# Communications.net
KiCad netlist of a schematic drawn in Altium Designer
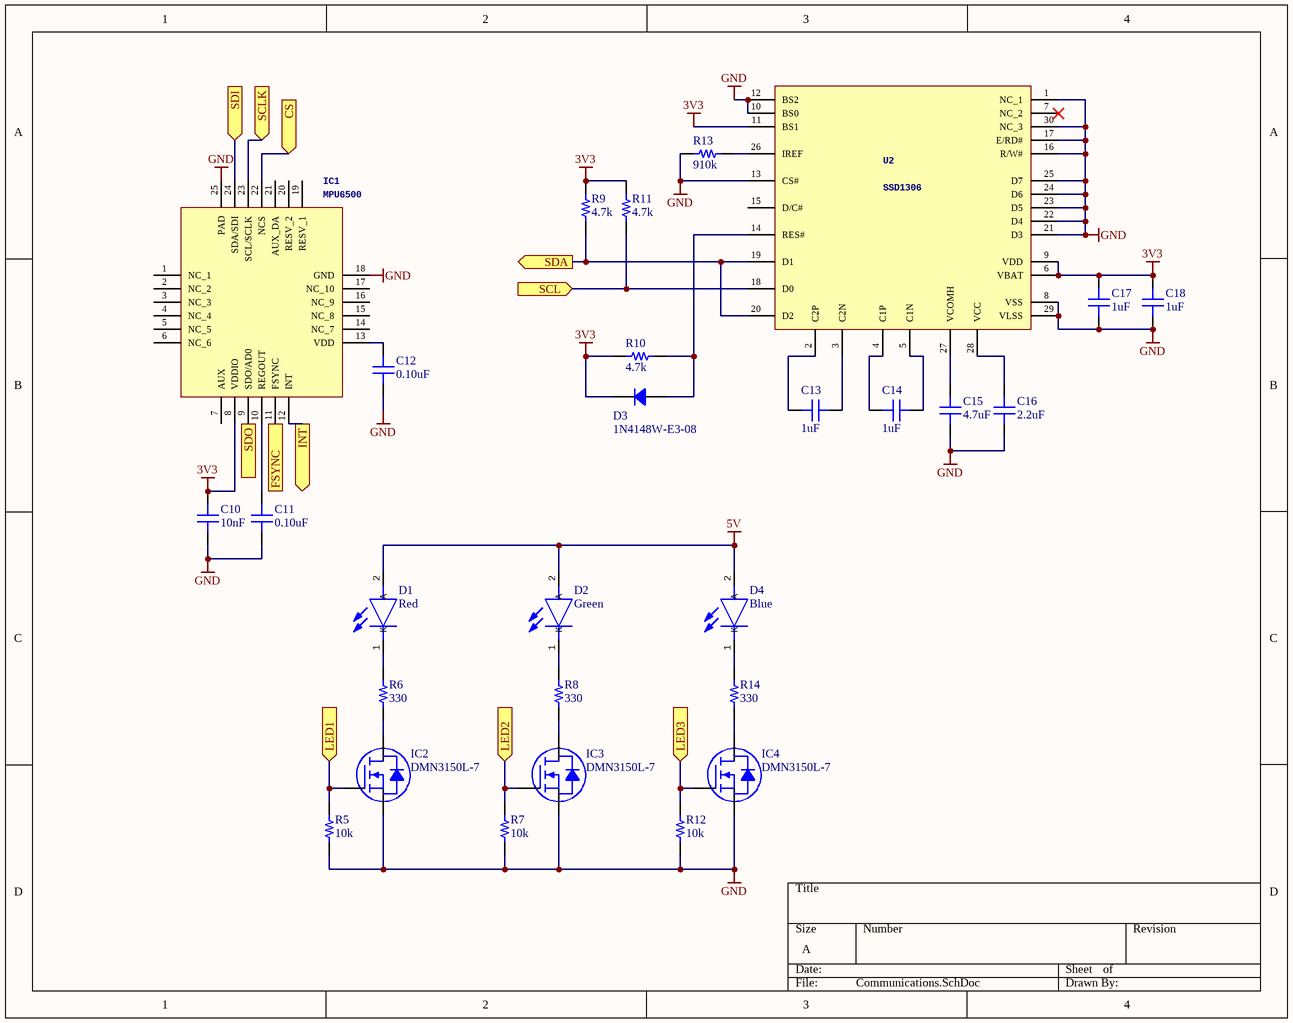
[diagram p0: Communications.SchDoc]

(export (version "E")
  (design (tool "Eeschema 10.0.6"))
  (components
    (comp (ref "C10")
      (value "10nF")
      (footprint "CAP 0402/1005")
      (description "CAP CER 10000PF 16V X7R 0402")
      (fields
        (field (name "PART NUMBER") "CL05B103KO5NNNC")
        (field (name "MANUFACTURER") "Samsung Electro-Mechanics America, Inc.")
      )
      (libsource (lib "Celestial Library Database") (part "Capacitor"))
    )
    (comp (ref "C11")
      (value "0.10uF")
      (footprint "CAP 0402/1005")
      (description "CAP CER 0.1UF 16V X7R 0402")
      (fields
        (field (name "PART NUMBER") "GCM155R71C104KA55D")
        (field (name "MANUFACTURER") "Murata Electronics North America")
      )
      (libsource (lib "Celestial Library Database") (part "Capacitor"))
    )
    (comp (ref "C12")
      (value "0.10uF")
      (footprint "CAP 0402/1005")
      (description "CAP CER 0.1UF 16V X7R 0402")
      (fields
        (field (name "PART NUMBER") "GCM155R71C104KA55D")
        (field (name "MANUFACTURER") "Murata Electronics North America")
      )
      (libsource (lib "Celestial Library Database") (part "Capacitor"))
    )
    (comp (ref "C13")
      (value "1uF")
      (footprint "CAP 0603/1608")
      (description "CAP CER 1UF 10V Y5V 0603")
      (fields
        (field (name "PART NUMBER") "CL10F105ZP8NNNC")
        (field (name "MANUFACTURER") "Samsung Electro-Mechanics America, Inc.")
      )
      (libsource (lib "Celestial Library Database") (part "Capacitor"))
    )
    (comp (ref "C14")
      (value "1uF")
      (footprint "CAP 0603/1608")
      (description "CAP CER 1UF 10V Y5V 0603")
      (fields
        (field (name "PART NUMBER") "CL10F105ZP8NNNC")
        (field (name "MANUFACTURER") "Samsung Electro-Mechanics America, Inc.")
      )
      (libsource (lib "Celestial Library Database") (part "Capacitor"))
    )
    (comp (ref "C15")
      (value "4.7uF")
      (footprint "CAP 0805/2012")
      (description "CAP CER 4.7UF 10V Y5V 0805")
      (fields (field (name "PART NUMBER") "CC0805ZRY5V6BB475") (field (name "MANUFACTURER") "Yageo"))
      (libsource (lib "Celestial Library Database") (part "Capacitor"))
    )
    (comp (ref "C16")
      (value "2.2uF")
      (footprint "CAP 0402/1005")
      (description "CAP CER 2.2UF 10V X5R 0402")
      (fields
        (field (name "PART NUMBER") "CL05A225KP5NSNC")
        (field (name "MANUFACTURER") "Samsung Electro-Mechanics America, Inc.")
      )
      (libsource (lib "Celestial Library Database") (part "Capacitor"))
    )
    (comp (ref "C17")
      (value "1uF")
      (footprint "CAP 0603/1608")
      (description "CAP CER 1UF 10V Y5V 0603")
      (fields
        (field (name "PART NUMBER") "CL10F105ZP8NNNC")
        (field (name "MANUFACTURER") "Samsung Electro-Mechanics America, Inc.")
      )
      (libsource (lib "Celestial Library Database") (part "Capacitor"))
    )
    (comp (ref "C18")
      (value "1uF")
      (footprint "CAP 0603/1608")
      (description "CAP CER 1UF 10V Y5V 0603")
      (fields
        (field (name "PART NUMBER") "CL10F105ZP8NNNC")
        (field (name "MANUFACTURER") "Samsung Electro-Mechanics America, Inc.")
      )
      (libsource (lib "Celestial Library Database") (part "Capacitor"))
    )
    (comp (ref "D1")
      (value "Red")
      (footprint "LTST")
      (libsource (lib "micromousev2Parts") (part "GENERIC_LED"))
    )
    (comp (ref "D2")
      (value "Green")
      (footprint "LTST")
      (libsource (lib "micromousev2Parts") (part "GENERIC_LED"))
    )
    (comp (ref "D3")
      (value "1N4148W-E3-08")
      (footprint "SOD-123")
      (description "DIODE GEN PURP 75V 150MA SOD123")
      (fields (field (name "MANUFACTURER") "Vishay Semiconductor Diodes Division"))
      (libsource (lib "Celestial Library Database") (part "Diode"))
    )
    (comp (ref "D4")
      (value "Blue")
      (footprint "LTST")
      (libsource (lib "micromousev2Parts") (part "GENERIC_LED"))
    )
    (comp (ref "IC1")
      (value "MPU6500")
      (footprint "QFN40P300X300X95-25N")
      (fields (field (name "ARROW_PART_NUMBER") "MPU-6500") (field (name "LIBRARYNAME") "micromousev2Parts"))
      (libsource (lib "micromousev2Parts") (part "MPU-6500"))
    )
    (comp (ref "IC2")
      (value "DMN3150L-7")
      (footprint "DIODES SOT-23-3")
      (description "MOSFET N-CH 28V 3.2A SOT23-3")
      (fields (field (name "MANUFACTURER") "Diodes Incorporated"))
      (libsource (lib "Celestial Library Database") (part "DIODES INC MOSFET N-CH SOT-23-3"))
    )
    (comp (ref "IC3")
      (value "DMN3150L-7")
      (footprint "DIODES SOT-23-3")
      (description "MOSFET N-CH 28V 3.2A SOT23-3")
      (fields (field (name "MANUFACTURER") "Diodes Incorporated"))
      (libsource (lib "Celestial Library Database") (part "DIODES INC MOSFET N-CH SOT-23-3"))
    )
    (comp (ref "IC4")
      (value "DMN3150L-7")
      (footprint "DIODES SOT-23-3")
      (description "MOSFET N-CH 28V 3.2A SOT23-3")
      (fields (field (name "MANUFACTURER") "Diodes Incorporated"))
      (libsource (lib "Celestial Library Database") (part "DIODES INC MOSFET N-CH SOT-23-3"))
    )
    (comp (ref "R5")
      (value "10k")
      (footprint "RES 0402/1005")
      (description "RES SMD 10K OHM 5% 1/16W 0402")
      (fields (field (name "PART NUMBER") "RC0402JR-0710KL") (field (name "MANUFACTURER") "Yageo"))
      (libsource (lib "Celestial Library Database") (part "Resistor"))
    )
    (comp (ref "R6")
      (value "330")
      (footprint "RES 0402/1005")
      (fields
        (field (name "PART NUMBER") "RMCF0402JT330R")
        (field (name "MANUFACTURER") "Stackpole Electronics Inc.")
      )
      (libsource (lib "Celestial Library Database") (part "Resistor"))
    )
    (comp (ref "R7")
      (value "10k")
      (footprint "RES 0402/1005")
      (description "RES SMD 10K OHM 5% 1/16W 0402")
      (fields (field (name "PART NUMBER") "RC0402JR-0710KL") (field (name "MANUFACTURER") "Yageo"))
      (libsource (lib "Celestial Library Database") (part "Resistor"))
    )
    (comp (ref "R8")
      (value "330")
      (footprint "RES 0402/1005")
      (fields
        (field (name "PART NUMBER") "RMCF0402JT330R")
        (field (name "MANUFACTURER") "Stackpole Electronics Inc.")
      )
      (libsource (lib "Celestial Library Database") (part "Resistor"))
    )
    (comp (ref "R9")
      (value "4.7k")
      (footprint "RES 0603/1608")
      (description "RES SMD 4.7K OHM 1% 1/10W 0603")
      (fields
        (field (name "PART NUMBER") "ERJ-3EKF4701V")
        (field (name "MANUFACTURER") "Panasonic Electronic Components")
      )
      (libsource (lib "Celestial Library Database") (part "Resistor"))
    )
    (comp (ref "R10")
      (value "4.7k")
      (footprint "RES 0603/1608")
      (description "RES SMD 4.7K OHM 1% 1/10W 0603")
      (fields
        (field (name "PART NUMBER") "ERJ-3EKF4701V")
        (field (name "MANUFACTURER") "Panasonic Electronic Components")
      )
      (libsource (lib "Celestial Library Database") (part "Resistor"))
    )
    (comp (ref "R11")
      (value "4.7k")
      (footprint "RES 0603/1608")
      (description "RES SMD 4.7K OHM 1% 1/10W 0603")
      (fields
        (field (name "PART NUMBER") "ERJ-3EKF4701V")
        (field (name "MANUFACTURER") "Panasonic Electronic Components")
      )
      (libsource (lib "Celestial Library Database") (part "Resistor"))
    )
    (comp (ref "R12")
      (value "10k")
      (footprint "RES 0402/1005")
      (description "RES SMD 10K OHM 5% 1/16W 0402")
      (fields (field (name "PART NUMBER") "RC0402JR-0710KL") (field (name "MANUFACTURER") "Yageo"))
      (libsource (lib "Celestial Library Database") (part "Resistor"))
    )
    (comp (ref "R13")
      (value "910k")
      (footprint "RES 0402/1005")
      (description "RES SMD 910K OHM 5% 1/10W 0402")
      (fields
        (field (name "PART NUMBER") "ERJ-2GEJ914X")
        (field (name "MANUFACTURER") "Panasonic Electronic Components")
      )
      (libsource (lib "Celestial Library Database") (part "Resistor"))
    )
    (comp (ref "R14")
      (value "330")
      (footprint "RES 0402/1005")
      (fields
        (field (name "PART NUMBER") "RMCF0402JT330R")
        (field (name "MANUFACTURER") "Stackpole Electronics Inc.")
      )
      (libsource (lib "Celestial Library Database") (part "Resistor"))
    )
    (comp (ref "U2")
      (value "SSD1306")
      (footprint "30PINFPC_P0.7MM")
      (fields (field (name "LIBRARYNAME") "micromousev2Parts"))
      (libsource (lib "micromousev2Parts") (part "SSD1306"))
    )
  )
  (nets
    (net (code "1") (name "/CS") (class "Default")
      (node (ref "IC1") (pin "22") (pinfunction "NCS_22") (pintype "passive"))
    )
    (net (code "2") (name "/FSYNC") (class "Default")
      (node (ref "IC1") (pin "11") (pinfunction "FSYNC_11") (pintype "passive"))
    )
    (net (code "3") (name "/INT") (class "Default")
      (node (ref "IC1") (pin "12") (pinfunction "INT_12") (pintype "passive"))
    )
    (net (code "4") (name "/LED1") (class "Default")
      (node (ref "IC2") (pin "1") (pinfunction "G_1") (pintype "passive"))
      (node (ref "R5") (pin "2") (pinfunction "2_2") (pintype "passive"))
    )
    (net (code "5") (name "/LED2") (class "Default")
      (node (ref "IC3") (pin "1") (pinfunction "G_1") (pintype "passive"))
      (node (ref "R7") (pin "2") (pinfunction "2_2") (pintype "passive"))
    )
    (net (code "6") (name "/LED3") (class "Default")
      (node (ref "IC4") (pin "1") (pinfunction "G_1") (pintype "passive"))
      (node (ref "R12") (pin "2") (pinfunction "2_2") (pintype "passive"))
    )
    (net (code "7") (name "/SCL") (class "Default")
      (node (ref "R11") (pin "1") (pinfunction "1_1") (pintype "passive"))
      (node (ref "U2") (pin "18") (pinfunction "D0_18") (pintype "passive"))
    )
    (net (code "8") (name "/SCLK") (class "Default")
      (node (ref "IC1") (pin "23") (pinfunction "SCL/SCLK_23") (pintype "passive"))
    )
    (net (code "9") (name "/SDA") (class "Default")
      (node (ref "R9") (pin "1") (pinfunction "1_1") (pintype "passive"))
      (node (ref "U2") (pin "19") (pinfunction "D1_19") (pintype "passive"))
      (node (ref "U2") (pin "20") (pinfunction "D2_20") (pintype "passive"))
    )
    (net (code "10") (name "/SDI") (class "Default")
      (node (ref "IC1") (pin "24") (pinfunction "SDA/SDI_24") (pintype "passive"))
    )
    (net (code "11") (name "/SDO") (class "Default")
      (node (ref "IC1") (pin "9") (pinfunction "SDO/AD0_9") (pintype "passive"))
    )
    (net (code "12") (name "3V3") (class "Default")
      (node (ref "C10") (pin "2") (pinfunction "2_2") (pintype "passive"))
      (node (ref "C17") (pin "2") (pinfunction "2_2") (pintype "passive"))
      (node (ref "C18") (pin "2") (pinfunction "2_2") (pintype "passive"))
      (node (ref "D3") (pin "2") (pinfunction "2_2") (pintype "passive"))
      (node (ref "IC1") (pin "8") (pinfunction "VDDIO_8") (pintype "passive"))
      (node (ref "R10") (pin "2") (pinfunction "2_2") (pintype "passive"))
      (node (ref "R11") (pin "2") (pinfunction "2_2") (pintype "passive"))
      (node (ref "R9") (pin "2") (pinfunction "2_2") (pintype "passive"))
      (node (ref "U2") (pin "11") (pinfunction "BS1_11") (pintype "passive"))
      (node (ref "U2") (pin "6") (pinfunction "VBAT_6") (pintype "passive"))
      (node (ref "U2") (pin "9") (pinfunction "VDD_9") (pintype "passive"))
    )
    (net (code "13") (name "5V") (class "Default")
      (node (ref "D1") (pin "2") (pinfunction "A_2") (pintype "passive"))
      (node (ref "D2") (pin "2") (pinfunction "A_2") (pintype "passive"))
      (node (ref "D4") (pin "2") (pinfunction "A_2") (pintype "passive"))
    )
    (net (code "14") (name "GND") (class "Default")
      (node (ref "C10") (pin "1") (pinfunction "1_1") (pintype "passive"))
      (node (ref "C11") (pin "1") (pinfunction "1_1") (pintype "passive"))
      (node (ref "C12") (pin "1") (pinfunction "1_1") (pintype "passive"))
      (node (ref "C15") (pin "1") (pinfunction "1_1") (pintype "passive"))
      (node (ref "C16") (pin "1") (pinfunction "1_1") (pintype "passive"))
      (node (ref "C17") (pin "1") (pinfunction "1_1") (pintype "passive"))
      (node (ref "C18") (pin "1") (pinfunction "1_1") (pintype "passive"))
      (node (ref "IC1") (pin "18") (pinfunction "GND_18") (pintype "passive"))
      (node (ref "IC1") (pin "25") (pinfunction "PAD_25") (pintype "passive"))
      (node (ref "IC2") (pin "3") (pinfunction "S_3") (pintype "passive"))
      (node (ref "IC3") (pin "3") (pinfunction "S_3") (pintype "passive"))
      (node (ref "IC4") (pin "3") (pinfunction "S_3") (pintype "passive"))
      (node (ref "R12") (pin "1") (pinfunction "1_1") (pintype "passive"))
      (node (ref "R13") (pin "1") (pinfunction "1_1") (pintype "passive"))
      (node (ref "R5") (pin "1") (pinfunction "1_1") (pintype "passive"))
      (node (ref "R7") (pin "1") (pinfunction "1_1") (pintype "passive"))
      (node (ref "U2") (pin "1") (pinfunction "NC_1_1") (pintype "passive"))
      (node (ref "U2") (pin "10") (pinfunction "BS0_10") (pintype "passive"))
      (node (ref "U2") (pin "12") (pinfunction "BS2_12") (pintype "passive"))
      (node (ref "U2") (pin "13") (pinfunction "CS#_13") (pintype "passive"))
      (node (ref "U2") (pin "16") (pinfunction "R/W#_16") (pintype "passive"))
      (node (ref "U2") (pin "17") (pinfunction "E/RD#_17") (pintype "passive"))
      (node (ref "U2") (pin "21") (pinfunction "D3_21") (pintype "passive"))
      (node (ref "U2") (pin "22") (pinfunction "D4_22") (pintype "passive"))
      (node (ref "U2") (pin "23") (pinfunction "D5_23") (pintype "passive"))
      (node (ref "U2") (pin "24") (pinfunction "D6_24") (pintype "passive"))
      (node (ref "U2") (pin "25") (pinfunction "D7_25") (pintype "passive"))
      (node (ref "U2") (pin "29") (pinfunction "VLSS_29") (pintype "passive"))
      (node (ref "U2") (pin "30") (pinfunction "NC_3_30") (pintype "passive"))
      (node (ref "U2") (pin "8") (pinfunction "VSS_8") (pintype "passive"))
    )
    (net (code "15") (name "Net-(D1-K)") (class "Default")
      (node (ref "D1") (pin "1") (pinfunction "K_1") (pintype "passive"))
      (node (ref "R6") (pin "2") (pinfunction "2_2") (pintype "passive"))
    )
    (net (code "16") (name "Net-(D2-K)") (class "Default")
      (node (ref "D2") (pin "1") (pinfunction "K_1") (pintype "passive"))
      (node (ref "R8") (pin "2") (pinfunction "2_2") (pintype "passive"))
    )
    (net (code "17") (name "Net-(D4-K)") (class "Default")
      (node (ref "D4") (pin "1") (pinfunction "K_1") (pintype "passive"))
      (node (ref "R14") (pin "2") (pinfunction "2_2") (pintype "passive"))
    )
    (net (code "18") (name "Net-(IC1-REGOUT)") (class "Default")
      (node (ref "C11") (pin "2") (pinfunction "2_2") (pintype "passive"))
      (node (ref "IC1") (pin "10") (pinfunction "REGOUT_10") (pintype "passive"))
    )
    (net (code "19") (name "Net-(IC1-VDD)") (class "Default")
      (node (ref "C12") (pin "2") (pinfunction "2_2") (pintype "passive"))
      (node (ref "IC1") (pin "13") (pinfunction "VDD_13") (pintype "passive"))
    )
    (net (code "20") (name "Net-(IC2-D)") (class "Default")
      (node (ref "IC2") (pin "2") (pinfunction "D_2") (pintype "passive"))
      (node (ref "R6") (pin "1") (pinfunction "1_1") (pintype "passive"))
    )
    (net (code "21") (name "Net-(IC3-D)") (class "Default")
      (node (ref "IC3") (pin "2") (pinfunction "D_2") (pintype "passive"))
      (node (ref "R8") (pin "1") (pinfunction "1_1") (pintype "passive"))
    )
    (net (code "22") (name "Net-(IC4-D)") (class "Default")
      (node (ref "IC4") (pin "2") (pinfunction "D_2") (pintype "passive"))
      (node (ref "R14") (pin "1") (pinfunction "1_1") (pintype "passive"))
    )
    (net (code "23") (name "Net-(U2-C1N)") (class "Default")
      (node (ref "C14") (pin "2") (pinfunction "2_2") (pintype "passive"))
      (node (ref "U2") (pin "5") (pinfunction "C1N_5") (pintype "passive"))
    )
    (net (code "24") (name "Net-(U2-C1P)") (class "Default")
      (node (ref "C14") (pin "1") (pinfunction "1_1") (pintype "passive"))
      (node (ref "U2") (pin "4") (pinfunction "C1P_4") (pintype "passive"))
    )
    (net (code "25") (name "Net-(U2-C2N)") (class "Default")
      (node (ref "C13") (pin "2") (pinfunction "2_2") (pintype "passive"))
      (node (ref "U2") (pin "3") (pinfunction "C2N_3") (pintype "passive"))
    )
    (net (code "26") (name "Net-(U2-C2P)") (class "Default")
      (node (ref "C13") (pin "1") (pinfunction "1_1") (pintype "passive"))
      (node (ref "U2") (pin "2") (pinfunction "C2P_2") (pintype "passive"))
    )
    (net (code "27") (name "Net-(U2-IREF)") (class "Default")
      (node (ref "R13") (pin "2") (pinfunction "2_2") (pintype "passive"))
      (node (ref "U2") (pin "26") (pinfunction "IREF_26") (pintype "passive"))
    )
    (net (code "28") (name "Net-(U2-RES#)") (class "Default")
      (node (ref "D3") (pin "1") (pinfunction "1_1") (pintype "passive"))
      (node (ref "R10") (pin "1") (pinfunction "1_1") (pintype "passive"))
      (node (ref "U2") (pin "14") (pinfunction "RES#_14") (pintype "passive"))
    )
    (net (code "29") (name "Net-(U2-VCC)") (class "Default")
      (node (ref "C16") (pin "2") (pinfunction "2_2") (pintype "passive"))
      (node (ref "U2") (pin "28") (pinfunction "VCC_28") (pintype "passive"))
    )
    (net (code "30") (name "Net-(U2-VCOMH)") (class "Default")
      (node (ref "C15") (pin "2") (pinfunction "2_2") (pintype "passive"))
      (node (ref "U2") (pin "27") (pinfunction "VCOMH_27") (pintype "passive"))
    )
    (net (code "31") (name "unconnected-(IC1-AUX-Pad7)") (class "Default")
      (node (ref "IC1") (pin "7") (pinfunction "AUX_7") (pintype "passive"))
    )
    (net (code "32") (name "unconnected-(IC1-AUX_DA-Pad21)") (class "Default")
      (node (ref "IC1") (pin "21") (pinfunction "AUX_DA_21") (pintype "passive"))
    )
    (net (code "33") (name "unconnected-(IC1-NC_1-Pad1)") (class "Default")
      (node (ref "IC1") (pin "1") (pinfunction "NC_1_1") (pintype "passive"))
    )
    (net (code "34") (name "unconnected-(IC1-NC_2-Pad2)") (class "Default")
      (node (ref "IC1") (pin "2") (pinfunction "NC_2_2") (pintype "passive"))
    )
    (net (code "35") (name "unconnected-(IC1-NC_3-Pad3)") (class "Default")
      (node (ref "IC1") (pin "3") (pinfunction "NC_3_3") (pintype "passive"))
    )
    (net (code "36") (name "unconnected-(IC1-NC_4-Pad4)") (class "Default")
      (node (ref "IC1") (pin "4") (pinfunction "NC_4_4") (pintype "passive"))
    )
    (net (code "37") (name "unconnected-(IC1-NC_5-Pad5)") (class "Default")
      (node (ref "IC1") (pin "5") (pinfunction "NC_5_5") (pintype "passive"))
    )
    (net (code "38") (name "unconnected-(IC1-NC_6-Pad6)") (class "Default")
      (node (ref "IC1") (pin "6") (pinfunction "NC_6_6") (pintype "passive"))
    )
    (net (code "39") (name "unconnected-(IC1-NC_7-Pad14)") (class "Default")
      (node (ref "IC1") (pin "14") (pinfunction "NC_7_14") (pintype "passive"))
    )
    (net (code "40") (name "unconnected-(IC1-NC_8-Pad15)") (class "Default")
      (node (ref "IC1") (pin "15") (pinfunction "NC_8_15") (pintype "passive"))
    )
    (net (code "41") (name "unconnected-(IC1-NC_9-Pad16)") (class "Default")
      (node (ref "IC1") (pin "16") (pinfunction "NC_9_16") (pintype "passive"))
    )
    (net (code "42") (name "unconnected-(IC1-NC_10-Pad17)") (class "Default")
      (node (ref "IC1") (pin "17") (pinfunction "NC_10_17") (pintype "passive"))
    )
    (net (code "43") (name "unconnected-(IC1-RESV_1-Pad19)") (class "Default")
      (node (ref "IC1") (pin "19") (pinfunction "RESV_1_19") (pintype "passive"))
    )
    (net (code "44") (name "unconnected-(IC1-RESV_2-Pad20)") (class "Default")
      (node (ref "IC1") (pin "20") (pinfunction "RESV_2_20") (pintype "passive"))
    )
    (net (code "45") (name "unconnected-(U2-D{slash}C#-Pad15)") (class "Default")
      (node (ref "U2") (pin "15") (pinfunction "D/C#_15") (pintype "passive"))
    )
    (net (code "46") (name "unconnected-(U2-NC_2-Pad7)") (class "Default")
      (node (ref "U2") (pin "7") (pinfunction "NC_2_7") (pintype "passive+no_connect"))
    )
  )
)
